# ESP32-Interfacesv02b.net
KiCad netlist of a schematic drawn in Altium Designer
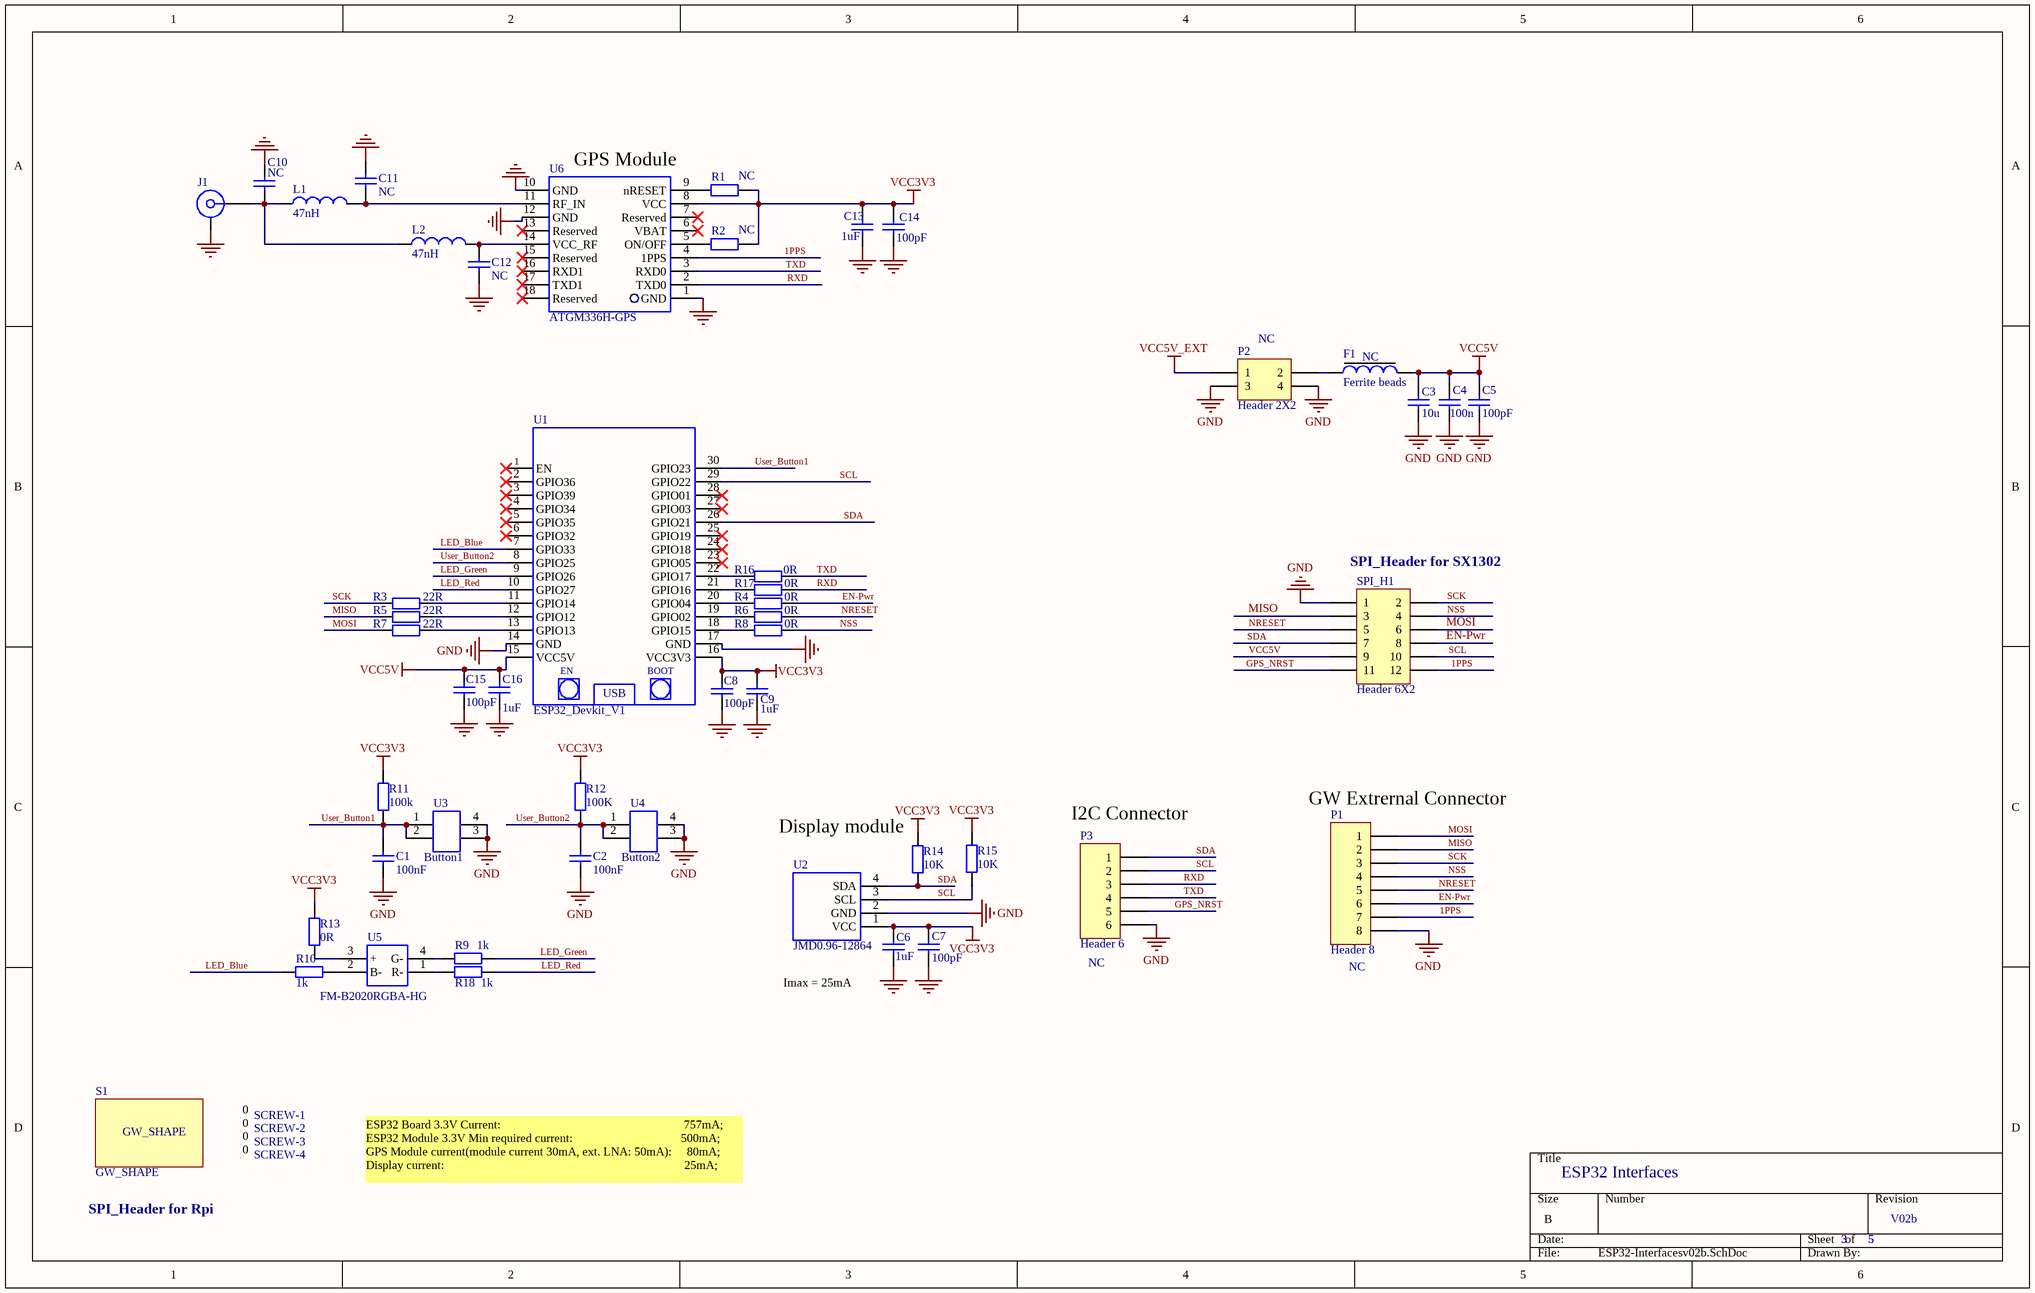
[diagram p0: ESP32-Interfacesv02b.SchDoc]

(export (version "E")
  (design (tool "Eeschema 10.0.6"))
  (components
    (comp (ref "C1")
      (value "100nF")
      (footprint "rlc_603_smd")
      (description "Capacitor SMD")
      (fields (field (name "Comment") "Cap") (field (name "PUBLISHER") "Altium Limited"))
      (libsource (lib "SX126x_e449v01a") (part "Cap"))
    )
    (comp (ref "C2")
      (value "100nF")
      (footprint "rlc_603_smd")
      (description "Capacitor SMD")
      (fields (field (name "Comment") "Cap") (field (name "PUBLISHER") "Altium Limited"))
      (libsource (lib "SX126x_e449v01a") (part "Cap"))
    )
    (comp (ref "C3")
      (value "10u")
      (footprint "rlc_805_smd")
      (description "Capacitor SMD")
      (fields (field (name "Comment") "Cap") (field (name "PUBLISHER") "Altium Limited"))
      (libsource (lib "SX126x_e449v01a") (part "Cap"))
    )
    (comp (ref "C4")
      (value "100n")
      (footprint "rlc_603_smd")
      (description "Capacitor SMD")
      (fields (field (name "Comment") "Cap") (field (name "PUBLISHER") "Altium Limited"))
      (libsource (lib "SX126x_e449v01a") (part "Cap"))
    )
    (comp (ref "C5")
      (value "100pF")
      (footprint "rlc_603_smd")
      (description "Capacitor SMD")
      (fields (field (name "Comment") "Cap") (field (name "PUBLISHER") "Altium Limited"))
      (libsource (lib "SX126x_e449v01a") (part "Cap"))
    )
    (comp (ref "C6")
      (value "1uF")
      (footprint "rlc_603_smd")
      (description "Capacitor SMD")
      (fields (field (name "Comment") "Cap") (field (name "PUBLISHER") "Altium Limited"))
      (libsource (lib "SX126x_e449v01a") (part "Cap"))
    )
    (comp (ref "C7")
      (value "100pF")
      (footprint "rlc_603_smd")
      (description "Capacitor SMD")
      (fields (field (name "Comment") "Cap") (field (name "PUBLISHER") "Altium Limited"))
      (libsource (lib "SX126x_e449v01a") (part "Cap"))
    )
    (comp (ref "C8")
      (value "100pF")
      (footprint "rlc_603_smd")
      (description "Capacitor SMD")
      (fields (field (name "Comment") "Cap") (field (name "PUBLISHER") "Altium Limited"))
      (libsource (lib "SX126x_e449v01a") (part "Cap"))
    )
    (comp (ref "C9")
      (value "1uF")
      (footprint "rlc_603_smd")
      (description "Capacitor SMD")
      (fields (field (name "Comment") "Cap") (field (name "PUBLISHER") "Altium Limited"))
      (libsource (lib "SX126x_e449v01a") (part "Cap"))
    )
    (comp (ref "C10")
      (value "NC")
      (footprint "rlc_402_smd")
      (description "Capacitor SMD")
      (fields (field (name "Comment") "Cap") (field (name "PUBLISHER") "Altium Limited"))
      (libsource (lib "SX126x_e449v01a") (part "Cap"))
    )
    (comp (ref "C11")
      (value "NC")
      (footprint "rlc_402_smd")
      (description "Capacitor SMD")
      (fields (field (name "Comment") "Cap") (field (name "PUBLISHER") "Altium Limited"))
      (libsource (lib "SX126x_e449v01a") (part "Cap"))
    )
    (comp (ref "C12")
      (value "NC")
      (footprint "rlc_402_smd")
      (description "Capacitor SMD")
      (fields (field (name "Comment") "Cap") (field (name "PUBLISHER") "Altium Limited"))
      (libsource (lib "SX126x_e449v01a") (part "Cap"))
    )
    (comp (ref "C13")
      (value "1uF")
      (footprint "rlc_603_smd")
      (description "Capacitor SMD")
      (fields (field (name "Comment") "Cap") (field (name "PUBLISHER") "Altium Limited"))
      (libsource (lib "SX126x_e449v01a") (part "Cap"))
    )
    (comp (ref "C14")
      (value "100pF")
      (footprint "rlc_603_smd")
      (description "Capacitor SMD")
      (fields (field (name "Comment") "Cap") (field (name "PUBLISHER") "Altium Limited"))
      (libsource (lib "SX126x_e449v01a") (part "Cap"))
    )
    (comp (ref "C15")
      (value "100pF")
      (footprint "rlc_603_smd")
      (description "Capacitor SMD")
      (fields (field (name "Comment") "Cap") (field (name "PUBLISHER") "Altium Limited"))
      (libsource (lib "SX126x_e449v01a") (part "Cap"))
    )
    (comp (ref "C16")
      (value "1uF")
      (footprint "rlc_603_smd")
      (description "Capacitor SMD")
      (fields (field (name "Comment") "Cap") (field (name "PUBLISHER") "Altium Limited"))
      (libsource (lib "SX126x_e449v01a") (part "Cap"))
    )
    (comp (ref "F1")
      (value "Ferrite beads")
      (footprint "rlc_603_smd")
      (fields (field (name "ALTIUM_VALUE") "NC"))
      (libsource (lib "SX126x_e449v01a") (part "Ferrite beads"))
    )
    (comp (ref "J1")
      (value "32K145-400L5")
      (footprint "ROS-32K145-400L5_V")
      (description "SMA Right Angle Jack, Edge Mount, Up to 18 GHz, -55 to 155 degC")
      (libsource (lib "Rosenberger SMA") (part "32K145-400L5"))
    )
    (comp (ref "L1")
      (value "47nH")
      (footprint "rlc_402_smd")
      (description "Inductor SMD")
      (fields (field (name "Comment") "Inductor") (field (name "PUBLISHER") "Altium Limited"))
      (libsource (lib "SX126x_e449v01a") (part "Inductor"))
    )
    (comp (ref "L2")
      (value "47nH")
      (footprint "rlc_402_smd")
      (description "Inductor SMD")
      (fields (field (name "Comment") "Inductor") (field (name "PUBLISHER") "Altium Limited"))
      (libsource (lib "SX126x_e449v01a") (part "Inductor"))
    )
    (comp (ref "P1")
      (value "Header 8")
      (footprint "HDR1X8")
      (description "Header, 8-Pin")
      (fields (field (name "PUBLISHER") "Altium Limited"))
      (libsource (lib "Miscellaneous Connectors") (part "Header 8"))
    )
    (comp (ref "P2")
      (value "Header 2X2")
      (footprint "HDR2X2")
      (description "Header, 2-Pin, Dual row")
      (fields (field (name "PUBLISHER") "Altium Limited"))
      (libsource (lib "Miscellaneous Connectors") (part "Header 2X2"))
    )
    (comp (ref "P3")
      (value "Header 6")
      (footprint "HDR1X6")
      (description "Header, 6-Pin")
      (fields (field (name "PUBLISHER") "Altium Limited"))
      (libsource (lib "Miscellaneous Connectors") (part "Header 6"))
    )
    (comp (ref "R1")
      (value "NC")
      (footprint "rlc_402_smd")
      (description "Resistor SMD - IEC symbol version")
      (fields (field (name "Comment") "Resistor"))
      (libsource (lib "SX126x_e449v01a") (part "Resistor"))
    )
    (comp (ref "R2")
      (value "NC")
      (footprint "rlc_402_smd")
      (description "Resistor SMD - IEC symbol version")
      (fields (field (name "Comment") "Resistor"))
      (libsource (lib "SX126x_e449v01a") (part "Resistor"))
    )
    (comp (ref "R3")
      (value "22R")
      (footprint "rlc_402_smd")
      (description "Resistor SMD - IEC symbol version")
      (fields (field (name "Comment") "Resistor"))
      (libsource (lib "SX126x_e449v01a") (part "Resistor"))
    )
    (comp (ref "R4")
      (value "0R")
      (footprint "rlc_402_smd")
      (description "Resistor SMD - IEC symbol version")
      (fields (field (name "Comment") "Resistor"))
      (libsource (lib "SX126x_e449v01a") (part "Resistor"))
    )
    (comp (ref "R5")
      (value "22R")
      (footprint "rlc_402_smd")
      (description "Resistor SMD - IEC symbol version")
      (fields (field (name "Comment") "Resistor"))
      (libsource (lib "SX126x_e449v01a") (part "Resistor"))
    )
    (comp (ref "R6")
      (value "0R")
      (footprint "rlc_402_smd")
      (description "Resistor SMD - IEC symbol version")
      (fields (field (name "Comment") "Resistor"))
      (libsource (lib "SX126x_e449v01a") (part "Resistor"))
    )
    (comp (ref "R7")
      (value "22R")
      (footprint "rlc_402_smd")
      (description "Resistor SMD - IEC symbol version")
      (fields (field (name "Comment") "Resistor"))
      (libsource (lib "SX126x_e449v01a") (part "Resistor"))
    )
    (comp (ref "R8")
      (value "0R")
      (footprint "rlc_402_smd")
      (description "Resistor SMD - IEC symbol version")
      (fields (field (name "Comment") "Resistor"))
      (libsource (lib "SX126x_e449v01a") (part "Resistor"))
    )
    (comp (ref "R9")
      (value "1k")
      (footprint "rlc_402_smd")
      (description "Resistor SMD - IEC symbol version")
      (fields (field (name "Comment") "Resistor"))
      (libsource (lib "") (part "Resistor_3"))
    )
    (comp (ref "R10")
      (value "1k")
      (footprint "rlc_402_smd")
      (description "Resistor SMD - IEC symbol version")
      (fields (field (name "Comment") "Resistor"))
      (libsource (lib "") (part "Resistor_3"))
    )
    (comp (ref "R11")
      (value "100k")
      (footprint "rlc_402_smd")
      (description "Resistor SMD - IEC symbol version")
      (fields (field (name "Comment") "Resistor"))
      (libsource (lib "") (part "Resistor_2"))
    )
    (comp (ref "R12")
      (value "100K")
      (footprint "rlc_402_smd")
      (description "Resistor SMD - IEC symbol version")
      (fields (field (name "Comment") "Resistor"))
      (libsource (lib "") (part "Resistor_2"))
    )
    (comp (ref "R13")
      (value "0R")
      (footprint "rlc_402_smd")
      (description "Resistor SMD - IEC symbol version")
      (fields (field (name "Comment") "Resistor"))
      (libsource (lib "") (part "Resistor_1"))
    )
    (comp (ref "R14")
      (value "10K")
      (footprint "rlc_402_smd")
      (description "Resistor SMD - IEC symbol version")
      (fields (field (name "Comment") "Resistor"))
      (libsource (lib "") (part "Resistor_2"))
    )
    (comp (ref "R15")
      (value "10K")
      (footprint "rlc_402_smd")
      (description "Resistor SMD - IEC symbol version")
      (fields (field (name "Comment") "Resistor"))
      (libsource (lib "") (part "Resistor_2"))
    )
    (comp (ref "R16")
      (value "0R")
      (footprint "rlc_402_smd")
      (description "Resistor SMD - IEC symbol version")
      (fields (field (name "Comment") "Resistor"))
      (libsource (lib "SX126x_e449v01a") (part "Resistor"))
    )
    (comp (ref "R17")
      (value "0R")
      (footprint "rlc_402_smd")
      (description "Resistor SMD - IEC symbol version")
      (fields (field (name "Comment") "Resistor"))
      (libsource (lib "SX126x_e449v01a") (part "Resistor"))
    )
    (comp (ref "R18")
      (value "1k")
      (footprint "rlc_402_smd")
      (description "Resistor SMD - IEC symbol version")
      (fields (field (name "Comment") "Resistor"))
      (libsource (lib "") (part "Resistor_3"))
    )
    (comp (ref "S1")
      (value "GW_SHAPE")
      (footprint "GW_SHAPE")
      (fields (field (name "PUBLISHER") "Altium Limited"))
      (libsource (lib "SX1302_e543v01a_1") (part "GW_SHAPE"))
    )
    (comp (ref "SCREW-1")
      (value "Logo symbol")
      (footprint "screw-M3")
      (description "Schematic symbol for Logo")
      (libsource (lib "SX1302_e520v01a") (part "Logo"))
    )
    (comp (ref "SCREW-2")
      (value "Logo symbol")
      (footprint "SCREW-M3")
      (description "Schematic symbol for Logo")
      (libsource (lib "SX1302_e520v01a") (part "Logo"))
    )
    (comp (ref "SCREW-3")
      (value "Logo symbol")
      (footprint "screw-M3")
      (description "Schematic symbol for Logo")
      (libsource (lib "SX1302_e520v01a") (part "Logo"))
    )
    (comp (ref "SCREW-4")
      (value "Logo symbol")
      (footprint "SCREW-M3")
      (description "Schematic symbol for Logo")
      (libsource (lib "SX1302_e520v01a") (part "Logo"))
    )
    (comp (ref "SPI_H1")
      (value "Header 6X2")
      (footprint "header_6_2_2.0")
      (description "Header, 12-Pin, Dual row")
      (fields (field (name "PUBLISHER") "Altium Limited"))
      (libsource (lib "SX1302_e543v01a") (part "Header 6X2"))
    )
    (comp (ref "U1")
      (value "ESP32_Devkit_V1")
      (footprint "ESP32-DOIT-30")
      (libsource (lib "Alex_Yang_Lib") (part "ESP32_Devkit_V1"))
    )
    (comp (ref "U2")
      (value "JMD0.96-12864")
      (footprint "JMD0.96_12864")
      (libsource (lib "Alex_Yang_Lib") (part "0.96oled-12864"))
    )
    (comp (ref "U3")
      (value "Button1")
      (footprint "TACT SWITCH_8HA-A-S1-01 - duplicate")
      (libsource (lib "Alex_Yang_Lib") (part "TACT SWITCH_8HA-A-S1-01"))
    )
    (comp (ref "U4")
      (value "Button2")
      (footprint "TACT SWITCH_8HA-A-S1-01 - duplicate")
      (libsource (lib "Alex_Yang_Lib") (part "TACT SWITCH_8HA-A-S1-01"))
    )
    (comp (ref "U5")
      (value "FM-B2020RGBA-HG")
      (footprint "RGB_2020")
      (libsource (lib "Alex_Yang_Lib") (part "RGB_LED"))
    )
    (comp (ref "U6")
      (value "ATGM336H-GPS")
      (footprint "ATGM336H")
      (libsource (lib "Alex_Yang_Lib") (part "ATGM336H"))
    )
  )
  (nets
    (net (code "1") (name "/1PPS") (class "Default")
      (node (ref "P1") (pin "7") (pinfunction "7_7") (pintype "passive"))
      (node (ref "SPI_H1") (pin "12") (pinfunction "12_12") (pintype "passive"))
      (node (ref "U6") (pin "4") (pinfunction "1PPS_4") (pintype "passive"))
    )
    (net (code "2") (name "/EN-Pwr") (class "Default")
      (node (ref "P1") (pin "6") (pinfunction "6_6") (pintype "passive"))
      (node (ref "R4") (pin "2") (pinfunction "2_2") (pintype "passive"))
      (node (ref "SPI_H1") (pin "8") (pinfunction "8_8") (pintype "passive"))
    )
    (net (code "3") (name "/GPS_NRST") (class "Default")
      (node (ref "P3") (pin "5") (pinfunction "5_5") (pintype "passive"))
      (node (ref "SPI_H1") (pin "11") (pinfunction "11_11") (pintype "passive"))
    )
    (net (code "4") (name "/LED_Blue") (class "Default")
      (node (ref "R10") (pin "2") (pinfunction "2_2") (pintype "passive"))
      (node (ref "U1") (pin "7") (pinfunction "GPIO33_7") (pintype "passive"))
    )
    (net (code "5") (name "/LED_Green") (class "Default")
      (node (ref "R9") (pin "1") (pinfunction "1_1") (pintype "passive"))
      (node (ref "U1") (pin "9") (pinfunction "GPIO26_9") (pintype "passive"))
    )
    (net (code "6") (name "/LED_Red") (class "Default")
      (node (ref "R18") (pin "1") (pinfunction "1_1") (pintype "passive"))
      (node (ref "U1") (pin "10") (pinfunction "GPIO27_10") (pintype "passive"))
    )
    (net (code "7") (name "/MISO") (class "Default")
      (node (ref "P1") (pin "2") (pinfunction "2_2") (pintype "passive"))
      (node (ref "R5") (pin "1") (pinfunction "1_1") (pintype "passive"))
      (node (ref "SPI_H1") (pin "3") (pinfunction "3_3") (pintype "passive"))
    )
    (net (code "8") (name "/MOSI") (class "Default")
      (node (ref "P1") (pin "1") (pinfunction "1_1") (pintype "passive"))
      (node (ref "R7") (pin "1") (pinfunction "1_1") (pintype "passive"))
      (node (ref "SPI_H1") (pin "6") (pinfunction "6_6") (pintype "passive"))
    )
    (net (code "9") (name "/NRESET") (class "Default")
      (node (ref "P1") (pin "5") (pinfunction "5_5") (pintype "passive"))
      (node (ref "R6") (pin "2") (pinfunction "2_2") (pintype "passive"))
      (node (ref "SPI_H1") (pin "5") (pinfunction "5_5") (pintype "passive"))
    )
    (net (code "10") (name "/NSS") (class "Default")
      (node (ref "P1") (pin "4") (pinfunction "4_4") (pintype "passive"))
      (node (ref "R8") (pin "2") (pinfunction "2_2") (pintype "passive"))
      (node (ref "SPI_H1") (pin "4") (pinfunction "4_4") (pintype "passive"))
    )
    (net (code "11") (name "/RXD") (class "Default")
      (node (ref "P3") (pin "3") (pinfunction "3_3") (pintype "passive"))
      (node (ref "R17") (pin "2") (pinfunction "2_2") (pintype "passive"))
      (node (ref "U6") (pin "2") (pinfunction "TXD0_2") (pintype "passive"))
    )
    (net (code "12") (name "/SCK") (class "Default")
      (node (ref "P1") (pin "3") (pinfunction "3_3") (pintype "passive"))
      (node (ref "R3") (pin "1") (pinfunction "1_1") (pintype "passive"))
      (node (ref "SPI_H1") (pin "2") (pinfunction "2_2") (pintype "passive"))
    )
    (net (code "13") (name "/SCL") (class "Default")
      (node (ref "P3") (pin "2") (pinfunction "2_2") (pintype "passive"))
      (node (ref "R15") (pin "2") (pinfunction "2_2") (pintype "passive"))
      (node (ref "SPI_H1") (pin "10") (pinfunction "10_10") (pintype "passive"))
      (node (ref "U1") (pin "29") (pinfunction "GPIO22_29") (pintype "passive"))
      (node (ref "U2") (pin "3") (pinfunction "SCL_3") (pintype "passive"))
    )
    (net (code "14") (name "/SDA") (class "Default")
      (node (ref "P3") (pin "1") (pinfunction "1_1") (pintype "passive"))
      (node (ref "R14") (pin "2") (pinfunction "2_2") (pintype "passive"))
      (node (ref "SPI_H1") (pin "7") (pinfunction "7_7") (pintype "passive"))
      (node (ref "U1") (pin "26") (pinfunction "GPIO21_26") (pintype "passive"))
      (node (ref "U2") (pin "4") (pinfunction "SDA_4") (pintype "passive"))
    )
    (net (code "15") (name "/TXD") (class "Default")
      (node (ref "P3") (pin "4") (pinfunction "4_4") (pintype "passive"))
      (node (ref "R16") (pin "2") (pinfunction "2_2") (pintype "passive"))
      (node (ref "U6") (pin "3") (pinfunction "RXD0_3") (pintype "passive"))
    )
    (net (code "16") (name "/User_Button1") (class "Default")
      (node (ref "C1") (pin "1") (pinfunction "1_1") (pintype "passive"))
      (node (ref "R11") (pin "2") (pinfunction "2_2") (pintype "passive"))
      (node (ref "U1") (pin "30") (pinfunction "GPIO23_30") (pintype "passive"))
      (node (ref "U3") (pin "1") (pintype "passive"))
      (node (ref "U3") (pin "2") (pintype "passive"))
    )
    (net (code "17") (name "/User_Button2") (class "Default")
      (node (ref "C2") (pin "1") (pinfunction "1_1") (pintype "passive"))
      (node (ref "R12") (pin "2") (pinfunction "2_2") (pintype "passive"))
      (node (ref "U1") (pin "8") (pinfunction "GPIO25_8") (pintype "passive"))
      (node (ref "U4") (pin "1") (pintype "passive"))
      (node (ref "U4") (pin "2") (pintype "passive"))
    )
    (net (code "18") (name "GND") (class "Default")
      (node (ref "C1") (pin "2") (pinfunction "2_2") (pintype "passive"))
      (node (ref "C10") (pin "2") (pinfunction "2_2") (pintype "passive"))
      (node (ref "C11") (pin "1") (pinfunction "1_1") (pintype "passive"))
      (node (ref "C12") (pin "1") (pinfunction "1_1") (pintype "passive"))
      (node (ref "C13") (pin "1") (pinfunction "1_1") (pintype "passive"))
      (node (ref "C14") (pin "1") (pinfunction "1_1") (pintype "passive"))
      (node (ref "C15") (pin "2") (pinfunction "2_2") (pintype "passive"))
      (node (ref "C16") (pin "2") (pinfunction "2_2") (pintype "passive"))
      (node (ref "C2") (pin "2") (pinfunction "2_2") (pintype "passive"))
      (node (ref "C3") (pin "1") (pinfunction "1_1") (pintype "passive"))
      (node (ref "C4") (pin "1") (pinfunction "1_1") (pintype "passive"))
      (node (ref "C5") (pin "1") (pinfunction "1_1") (pintype "passive"))
      (node (ref "C6") (pin "2") (pinfunction "2_2") (pintype "passive"))
      (node (ref "C7") (pin "2") (pinfunction "2_2") (pintype "passive"))
      (node (ref "C8") (pin "2") (pinfunction "2_2") (pintype "passive"))
      (node (ref "C9") (pin "2") (pinfunction "2_2") (pintype "passive"))
      (node (ref "J1") (pin "MP") (pinfunction "MP_MP") (pintype "passive"))
      (node (ref "P1") (pin "8") (pinfunction "8_8") (pintype "passive"))
      (node (ref "P2") (pin "3") (pinfunction "3_3") (pintype "passive"))
      (node (ref "P2") (pin "4") (pinfunction "4_4") (pintype "passive"))
      (node (ref "P3") (pin "6") (pinfunction "6_6") (pintype "passive"))
      (node (ref "SPI_H1") (pin "1") (pinfunction "1_1") (pintype "passive"))
      (node (ref "U1") (pin "14") (pinfunction "GND_14") (pintype "passive"))
      (node (ref "U1") (pin "17") (pinfunction "GND_17") (pintype "passive"))
      (node (ref "U2") (pin "2") (pinfunction "GND_2") (pintype "passive"))
      (node (ref "U3") (pin "3") (pintype "passive"))
      (node (ref "U3") (pin "4") (pintype "passive"))
      (node (ref "U4") (pin "3") (pintype "passive"))
      (node (ref "U4") (pin "4") (pintype "passive"))
      (node (ref "U6") (pin "1") (pinfunction "GND_1") (pintype "passive"))
      (node (ref "U6") (pin "10") (pinfunction "GND_10") (pintype "passive"))
      (node (ref "U6") (pin "12") (pinfunction "GND_12") (pintype "passive"))
    )
    (net (code "19") (name "Net-(C10-Pad1)") (class "Default")
      (node (ref "C10") (pin "1") (pinfunction "1_1") (pintype "passive"))
      (node (ref "J1") (pin "1") (pinfunction "1_1") (pintype "passive"))
      (node (ref "L1") (pin "1") (pinfunction "1_1") (pintype "passive"))
      (node (ref "L2") (pin "1") (pinfunction "1_1") (pintype "passive"))
    )
    (net (code "20") (name "Net-(F1-Pad1)") (class "Default")
      (node (ref "F1") (pin "1") (pinfunction "1_1") (pintype "passive"))
      (node (ref "P2") (pin "2") (pinfunction "2_2") (pintype "passive"))
    )
    (net (code "21") (name "Net-(U1-GPIO02)") (class "Default")
      (node (ref "R6") (pin "1") (pinfunction "1_1") (pintype "passive"))
      (node (ref "U1") (pin "19") (pinfunction "GPIO02_19") (pintype "passive"))
    )
    (net (code "22") (name "Net-(U1-GPIO04)") (class "Default")
      (node (ref "R4") (pin "1") (pinfunction "1_1") (pintype "passive"))
      (node (ref "U1") (pin "20") (pinfunction "GPIO04_20") (pintype "passive"))
    )
    (net (code "23") (name "Net-(U1-GPIO12)") (class "Default")
      (node (ref "R5") (pin "2") (pinfunction "2_2") (pintype "passive"))
      (node (ref "U1") (pin "12") (pinfunction "GPIO12_12") (pintype "passive"))
    )
    (net (code "24") (name "Net-(U1-GPIO13)") (class "Default")
      (node (ref "R7") (pin "2") (pinfunction "2_2") (pintype "passive"))
      (node (ref "U1") (pin "13") (pinfunction "GPIO13_13") (pintype "passive"))
    )
    (net (code "25") (name "Net-(U1-GPIO14)") (class "Default")
      (node (ref "R3") (pin "2") (pinfunction "2_2") (pintype "passive"))
      (node (ref "U1") (pin "11") (pinfunction "GPIO14_11") (pintype "passive"))
    )
    (net (code "26") (name "Net-(U1-GPIO15)") (class "Default")
      (node (ref "R8") (pin "1") (pinfunction "1_1") (pintype "passive"))
      (node (ref "U1") (pin "18") (pinfunction "GPIO15_18") (pintype "passive"))
    )
    (net (code "27") (name "Net-(U1-GPIO16)") (class "Default")
      (node (ref "R17") (pin "1") (pinfunction "1_1") (pintype "passive"))
      (node (ref "U1") (pin "21") (pinfunction "GPIO16_21") (pintype "passive"))
    )
    (net (code "28") (name "Net-(U1-GPIO17)") (class "Default")
      (node (ref "R16") (pin "1") (pinfunction "1_1") (pintype "passive"))
      (node (ref "U1") (pin "22") (pinfunction "GPIO17_22") (pintype "passive"))
    )
    (net (code "29") (name "Net-(U5-+)") (class "Default")
      (node (ref "R13") (pin "1") (pinfunction "1_1") (pintype "passive"))
      (node (ref "U5") (pin "3") (pinfunction "+_3") (pintype "passive"))
    )
    (net (code "30") (name "Net-(U5-B-)") (class "Default")
      (node (ref "R10") (pin "1") (pinfunction "1_1") (pintype "passive"))
      (node (ref "U5") (pin "2") (pinfunction "B-_2") (pintype "passive"))
    )
    (net (code "31") (name "Net-(U5-G-)") (class "Default")
      (node (ref "R9") (pin "2") (pinfunction "2_2") (pintype "passive"))
      (node (ref "U5") (pin "4") (pinfunction "G-_4") (pintype "passive"))
    )
    (net (code "32") (name "Net-(U5-R-)") (class "Default")
      (node (ref "R18") (pin "2") (pinfunction "2_2") (pintype "passive"))
      (node (ref "U5") (pin "1") (pinfunction "R-_1") (pintype "passive"))
    )
    (net (code "33") (name "Net-(U6-ON{slash}OFF)") (class "Default")
      (node (ref "R2") (pin "1") (pinfunction "1_1") (pintype "passive"))
      (node (ref "U6") (pin "5") (pinfunction "ON/OFF_5") (pintype "passive"))
    )
    (net (code "34") (name "Net-(U6-RF_IN)") (class "Default")
      (node (ref "C11") (pin "2") (pinfunction "2_2") (pintype "passive"))
      (node (ref "L1") (pin "2") (pinfunction "2_2") (pintype "passive"))
      (node (ref "U6") (pin "11") (pinfunction "RF_IN_11") (pintype "passive"))
    )
    (net (code "35") (name "Net-(U6-VCC_RF)") (class "Default")
      (node (ref "C12") (pin "2") (pinfunction "2_2") (pintype "passive"))
      (node (ref "L2") (pin "2") (pinfunction "2_2") (pintype "passive"))
      (node (ref "U6") (pin "14") (pinfunction "VCC_RF_14") (pintype "passive"))
    )
    (net (code "36") (name "Net-(U6-nRESET)") (class "Default")
      (node (ref "R1") (pin "1") (pinfunction "1_1") (pintype "passive"))
      (node (ref "U6") (pin "9") (pinfunction "nRESET_9") (pintype "passive"))
    )
    (net (code "37") (name "VCC3V3") (class "Default")
      (node (ref "C13") (pin "2") (pinfunction "2_2") (pintype "passive"))
      (node (ref "C14") (pin "2") (pinfunction "2_2") (pintype "passive"))
      (node (ref "C6") (pin "1") (pinfunction "1_1") (pintype "passive"))
      (node (ref "C7") (pin "1") (pinfunction "1_1") (pintype "passive"))
      (node (ref "C8") (pin "1") (pinfunction "1_1") (pintype "passive"))
      (node (ref "C9") (pin "1") (pinfunction "1_1") (pintype "passive"))
      (node (ref "R1") (pin "2") (pinfunction "2_2") (pintype "passive"))
      (node (ref "R11") (pin "1") (pinfunction "1_1") (pintype "passive"))
      (node (ref "R12") (pin "1") (pinfunction "1_1") (pintype "passive"))
      (node (ref "R13") (pin "2") (pinfunction "2_2") (pintype "passive"))
      (node (ref "R14") (pin "1") (pinfunction "1_1") (pintype "passive"))
      (node (ref "R15") (pin "1") (pinfunction "1_1") (pintype "passive"))
      (node (ref "R2") (pin "2") (pinfunction "2_2") (pintype "passive"))
      (node (ref "U1") (pin "16") (pinfunction "VCC3V3_16") (pintype "passive"))
      (node (ref "U2") (pin "1") (pinfunction "VCC_1") (pintype "passive"))
      (node (ref "U6") (pin "8") (pinfunction "VCC_8") (pintype "passive"))
    )
    (net (code "38") (name "VCC5V") (class "Default")
      (node (ref "C15") (pin "1") (pinfunction "1_1") (pintype "passive"))
      (node (ref "C16") (pin "1") (pinfunction "1_1") (pintype "passive"))
      (node (ref "C3") (pin "2") (pinfunction "2_2") (pintype "passive"))
      (node (ref "C4") (pin "2") (pinfunction "2_2") (pintype "passive"))
      (node (ref "C5") (pin "2") (pinfunction "2_2") (pintype "passive"))
      (node (ref "F1") (pin "2") (pinfunction "2_2") (pintype "passive"))
      (node (ref "SPI_H1") (pin "9") (pinfunction "9_9") (pintype "passive"))
      (node (ref "U1") (pin "15") (pinfunction "VCC5V_15") (pintype "passive"))
    )
    (net (code "39") (name "VCC5V_EXT") (class "Default")
      (node (ref "P2") (pin "1") (pinfunction "1_1") (pintype "passive"))
    )
    (net (code "40") (name "unconnected-(SCREW-1-Pad0)") (class "Default")
      (node (ref "SCREW-1") (pin "0") (pinfunction "0_0") (pintype "passive"))
    )
    (net (code "41") (name "unconnected-(SCREW-2-Pad0)") (class "Default")
      (node (ref "SCREW-2") (pin "0") (pinfunction "0_0") (pintype "passive"))
    )
    (net (code "42") (name "unconnected-(SCREW-3-Pad0)") (class "Default")
      (node (ref "SCREW-3") (pin "0") (pinfunction "0_0") (pintype "passive"))
    )
    (net (code "43") (name "unconnected-(SCREW-4-Pad0)") (class "Default")
      (node (ref "SCREW-4") (pin "0") (pinfunction "0_0") (pintype "passive"))
    )
    (net (code "44") (name "unconnected-(U1-EN-Pad1)") (class "Default")
      (node (ref "U1") (pin "1") (pinfunction "EN_1") (pintype "passive+no_connect"))
    )
    (net (code "45") (name "unconnected-(U1-GPIO01-Pad28)") (class "Default")
      (node (ref "U1") (pin "28") (pinfunction "GPIO01_28") (pintype "passive+no_connect"))
    )
    (net (code "46") (name "unconnected-(U1-GPIO03-Pad27)") (class "Default")
      (node (ref "U1") (pin "27") (pinfunction "GPIO03_27") (pintype "passive+no_connect"))
    )
    (net (code "47") (name "unconnected-(U1-GPIO05-Pad23)") (class "Default")
      (node (ref "U1") (pin "23") (pinfunction "GPIO05_23") (pintype "passive+no_connect"))
    )
    (net (code "48") (name "unconnected-(U1-GPIO18-Pad24)") (class "Default")
      (node (ref "U1") (pin "24") (pinfunction "GPIO18_24") (pintype "passive+no_connect"))
    )
    (net (code "49") (name "unconnected-(U1-GPIO19-Pad25)") (class "Default")
      (node (ref "U1") (pin "25") (pinfunction "GPIO19_25") (pintype "passive+no_connect"))
    )
    (net (code "50") (name "unconnected-(U1-GPIO32-Pad6)") (class "Default")
      (node (ref "U1") (pin "6") (pinfunction "GPIO32_6") (pintype "passive+no_connect"))
    )
    (net (code "51") (name "unconnected-(U1-GPIO34-Pad4)") (class "Default")
      (node (ref "U1") (pin "4") (pinfunction "GPIO34_4") (pintype "passive+no_connect"))
    )
    (net (code "52") (name "unconnected-(U1-GPIO35-Pad5)") (class "Default")
      (node (ref "U1") (pin "5") (pinfunction "GPIO35_5") (pintype "passive+no_connect"))
    )
    (net (code "53") (name "unconnected-(U1-GPIO36-Pad2)") (class "Default")
      (node (ref "U1") (pin "2") (pinfunction "GPIO36_2") (pintype "passive+no_connect"))
    )
    (net (code "54") (name "unconnected-(U1-GPIO39-Pad3)") (class "Default")
      (node (ref "U1") (pin "3") (pinfunction "GPIO39_3") (pintype "passive+no_connect"))
    )
    (net (code "55") (name "unconnected-(U6-RXD1-Pad16)") (class "Default")
      (node (ref "U6") (pin "16") (pinfunction "RXD1_16") (pintype "passive+no_connect"))
    )
    (net (code "56") (name "unconnected-(U6-Reserved-Pad7)") (class "Default")
      (node (ref "U6") (pin "7") (pinfunction "Reserved_7") (pintype "passive+no_connect"))
    )
    (net (code "57") (name "unconnected-(U6-Reserved-Pad13)") (class "Default")
      (node (ref "U6") (pin "13") (pinfunction "Reserved_13") (pintype "passive+no_connect"))
    )
    (net (code "58") (name "unconnected-(U6-Reserved-Pad15)") (class "Default")
      (node (ref "U6") (pin "15") (pinfunction "Reserved_15") (pintype "passive+no_connect"))
    )
    (net (code "59") (name "unconnected-(U6-Reserved-Pad18)") (class "Default")
      (node (ref "U6") (pin "18") (pinfunction "Reserved_18") (pintype "passive+no_connect"))
    )
    (net (code "60") (name "unconnected-(U6-TXD1-Pad17)") (class "Default")
      (node (ref "U6") (pin "17") (pinfunction "TXD1_17") (pintype "passive+no_connect"))
    )
    (net (code "61") (name "unconnected-(U6-VBAT-Pad6)") (class "Default")
      (node (ref "U6") (pin "6") (pinfunction "VBAT_6") (pintype "passive+no_connect"))
    )
  )
)
